# rp3a0-mini-misc.net
KiCad netlist of a schematic drawn in Altium Designer
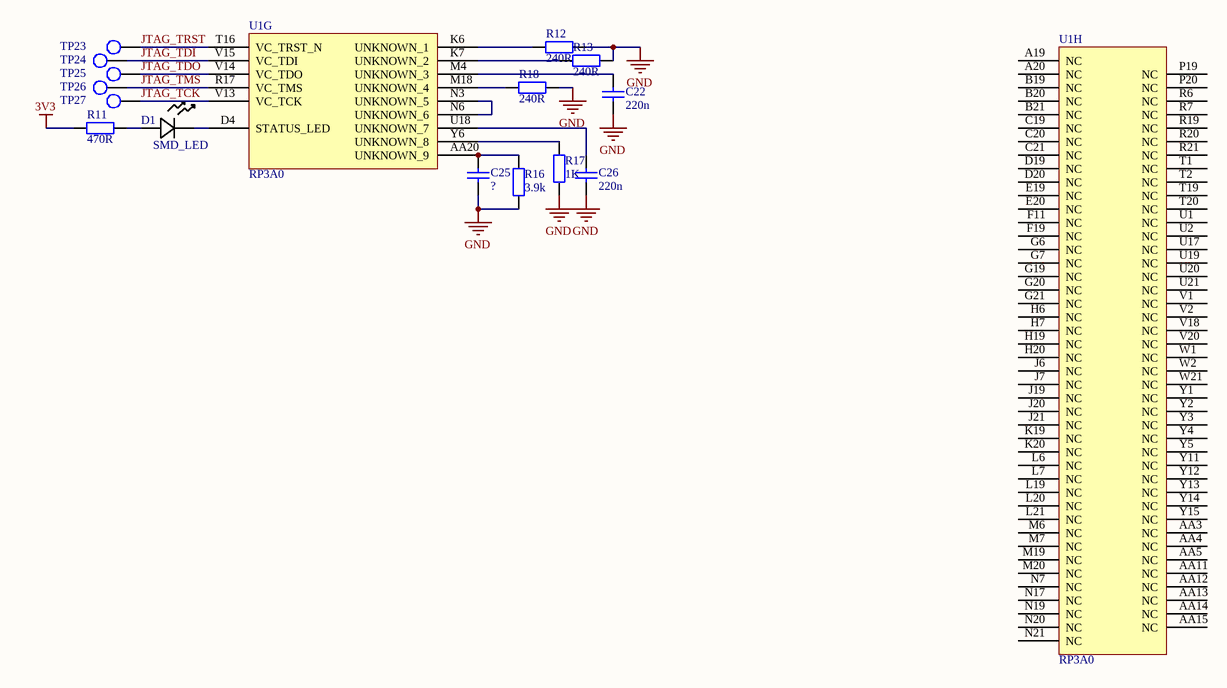
[diagram p0: rp3a0-mini-misc.SchDoc]

(export (version "E")
  (design (tool "Eeschema 10.0.6"))
  (components
    (comp (ref "C22")
      (value "220n")
      (footprint "0402")
      (description "Capacitor")
      (fields (field (name "Comment") "Cap"))
      (libsource (lib "custom-lib") (part "CAP-NONPOL"))
    )
    (comp (ref "C25")
      (value "?")
      (footprint "0402")
      (description "Capacitor")
      (fields (field (name "Comment") "Cap"))
      (libsource (lib "custom-lib") (part "CAP-NONPOL"))
    )
    (comp (ref "C26")
      (value "220n")
      (footprint "0402")
      (description "Capacitor")
      (fields (field (name "Comment") "Cap"))
      (libsource (lib "custom-lib") (part "CAP-NONPOL"))
    )
    (comp (ref "D1") (value "SMD_LED") (footprint "LED_0603") (libsource (lib "custom-lib") (part "SMD_LED")))
    (comp (ref "R11")
      (value "470R")
      (footprint "RES-0402-SML")
      (description "Resistor")
      (fields (field (name "Comment") "Res SMD"))
      (libsource (lib "custom-lib") (part "Res SMD"))
    )
    (comp (ref "R12")
      (value "240R")
      (footprint "RES-0402-SML")
      (description "Resistor")
      (fields (field (name "Comment") "Res SMD"))
      (libsource (lib "custom-lib") (part "Res SMD"))
    )
    (comp (ref "R13")
      (value "240R")
      (footprint "RES-0402-SML")
      (description "Resistor")
      (fields (field (name "Comment") "Res SMD"))
      (libsource (lib "custom-lib") (part "Res SMD"))
    )
    (comp (ref "R16")
      (value "3.9k")
      (footprint "RES-0402-SML")
      (description "Resistor")
      (fields (field (name "Comment") "Res SMD"))
      (libsource (lib "") (part "Res SMD_1"))
    )
    (comp (ref "R17")
      (value "1K")
      (footprint "RES-0402-SML")
      (description "Resistor")
      (fields (field (name "Comment") "Res SMD"))
      (libsource (lib "") (part "Res SMD_1"))
    )
    (comp (ref "R18")
      (value "240R")
      (footprint "RES-0402-SML")
      (description "Resistor")
      (fields (field (name "Comment") "Res SMD"))
      (libsource (lib "custom-lib") (part "Res SMD"))
    )
    (comp (ref "TP23")
      (value "TEST_POINT")
      (footprint "TEST_POINT_1.2MM")
      (description "Test point")
      (libsource (lib "custom-lib") (part "TEST_POINT"))
    )
    (comp (ref "TP24")
      (value "TEST_POINT")
      (footprint "TEST_POINT_1.2MM")
      (description "Test point")
      (libsource (lib "custom-lib") (part "TEST_POINT"))
    )
    (comp (ref "TP25")
      (value "TEST_POINT")
      (footprint "TEST_POINT_1.2MM")
      (description "Test point")
      (libsource (lib "custom-lib") (part "TEST_POINT"))
    )
    (comp (ref "TP26")
      (value "TEST_POINT")
      (footprint "TEST_POINT_1.2MM")
      (description "Test point")
      (libsource (lib "custom-lib") (part "TEST_POINT"))
    )
    (comp (ref "TP27")
      (value "TEST_POINT")
      (footprint "TEST_POINT_1.2MM")
      (description "Test point")
      (libsource (lib "custom-lib") (part "TEST_POINT"))
    )
    (comp (ref "U1") (value "RP3A0") (footprint "RP3A0-BGA") (libsource (lib "rp3a0") (part "RP3A0")))
  )
  (nets
    (net (code "1") (name "/JTAG_TCK") (class "Default")
      (node (ref "TP27") (pin "TP") (pintype "passive"))
      (node (ref "U1") (pin "V13") (pinfunction "VC_TCK_V13") (pintype "passive"))
    )
    (net (code "2") (name "/JTAG_TDI") (class "Default")
      (node (ref "TP24") (pin "TP") (pintype "passive"))
      (node (ref "U1") (pin "V15") (pinfunction "VC_TDI_V15") (pintype "passive"))
    )
    (net (code "3") (name "/JTAG_TDO") (class "Default")
      (node (ref "TP25") (pin "TP") (pintype "passive"))
      (node (ref "U1") (pin "V14") (pinfunction "VC_TDO_V14") (pintype "passive"))
    )
    (net (code "4") (name "/JTAG_TMS") (class "Default")
      (node (ref "TP26") (pin "TP") (pintype "passive"))
      (node (ref "U1") (pin "R17") (pinfunction "VC_TMS_R17") (pintype "passive"))
    )
    (net (code "5") (name "/JTAG_TRST") (class "Default")
      (node (ref "TP23") (pin "TP") (pintype "passive"))
      (node (ref "U1") (pin "T16") (pinfunction "VC_TRST_N_T16") (pintype "passive"))
    )
    (net (code "6") (name "3V3") (class "Default")
      (node (ref "R11") (pin "1") (pinfunction "1_1") (pintype "passive"))
    )
    (net (code "7") (name "GND") (class "Default")
      (node (ref "C22") (pin "1") (pinfunction "1_1") (pintype "passive"))
      (node (ref "C25") (pin "1") (pinfunction "1_1") (pintype "passive"))
      (node (ref "C26") (pin "1") (pinfunction "1_1") (pintype "passive"))
      (node (ref "R12") (pin "2") (pinfunction "2_2") (pintype "passive"))
      (node (ref "R13") (pin "2") (pinfunction "2_2") (pintype "passive"))
      (node (ref "R16") (pin "1") (pinfunction "1_1") (pintype "passive"))
      (node (ref "R17") (pin "1") (pinfunction "1_1") (pintype "passive"))
      (node (ref "R18") (pin "2") (pinfunction "2_2") (pintype "passive"))
    )
    (net (code "8") (name "Net-(D1-Pad1)") (class "Default")
      (node (ref "D1") (pin "1") (pinfunction "1_1") (pintype "passive"))
      (node (ref "R11") (pin "2") (pinfunction "2_2") (pintype "passive"))
    )
    (net (code "9") (name "Net-(U1G-STATUS_LED)") (class "Default")
      (node (ref "D1") (pin "2") (pinfunction "2_2") (pintype "passive"))
      (node (ref "U1") (pin "D4") (pinfunction "STATUS_LED_D4") (pintype "passive"))
    )
    (net (code "10") (name "Net-(U1G-UNKNOWN_1)") (class "Default")
      (node (ref "R12") (pin "1") (pinfunction "1_1") (pintype "passive"))
      (node (ref "U1") (pin "K6") (pinfunction "UNKNOWN_1_K6") (pintype "passive"))
    )
    (net (code "11") (name "Net-(U1G-UNKNOWN_2)") (class "Default")
      (node (ref "R13") (pin "1") (pinfunction "1_1") (pintype "passive"))
      (node (ref "U1") (pin "K7") (pinfunction "UNKNOWN_2_K7") (pintype "passive"))
    )
    (net (code "12") (name "Net-(U1G-UNKNOWN_3)") (class "Default")
      (node (ref "C22") (pin "2") (pinfunction "2_2") (pintype "passive"))
      (node (ref "U1") (pin "M4") (pinfunction "UNKNOWN_3_M4") (pintype "passive"))
    )
    (net (code "13") (name "Net-(U1G-UNKNOWN_4)") (class "Default")
      (node (ref "R18") (pin "1") (pinfunction "1_1") (pintype "passive"))
      (node (ref "U1") (pin "M18") (pinfunction "UNKNOWN_4_M18") (pintype "passive"))
    )
    (net (code "14") (name "Net-(U1G-UNKNOWN_5)") (class "Default")
      (node (ref "U1") (pin "N3") (pinfunction "UNKNOWN_5_N3") (pintype "passive"))
      (node (ref "U1") (pin "N6") (pinfunction "UNKNOWN_6_N6") (pintype "passive"))
    )
    (net (code "15") (name "Net-(U1G-UNKNOWN_7)") (class "Default")
      (node (ref "C26") (pin "2") (pinfunction "2_2") (pintype "passive"))
      (node (ref "U1") (pin "U18") (pinfunction "UNKNOWN_7_U18") (pintype "passive"))
    )
    (net (code "16") (name "Net-(U1G-UNKNOWN_8)") (class "Default")
      (node (ref "R17") (pin "2") (pinfunction "2_2") (pintype "passive"))
      (node (ref "U1") (pin "Y6") (pinfunction "UNKNOWN_8_Y6") (pintype "passive"))
    )
    (net (code "17") (name "Net-(U1G-UNKNOWN_9)") (class "Default")
      (node (ref "C25") (pin "2") (pinfunction "2_2") (pintype "passive"))
      (node (ref "R16") (pin "2") (pinfunction "2_2") (pintype "passive"))
      (node (ref "U1") (pin "AA20") (pinfunction "UNKNOWN_9_AA20") (pintype "passive"))
    )
    (net (code "18") (name "unconnected-(U1H-NC-PadA19)") (class "Default")
      (node (ref "U1") (pin "A19") (pinfunction "NC_A19") (pintype "passive"))
    )
    (net (code "19") (name "unconnected-(U1H-NC-PadA20)") (class "Default")
      (node (ref "U1") (pin "A20") (pinfunction "NC_A20") (pintype "passive"))
    )
    (net (code "20") (name "unconnected-(U1H-NC-PadAA3)") (class "Default")
      (node (ref "U1") (pin "AA3") (pinfunction "NC_AA3") (pintype "passive"))
    )
    (net (code "21") (name "unconnected-(U1H-NC-PadAA4)") (class "Default")
      (node (ref "U1") (pin "AA4") (pinfunction "NC_AA4") (pintype "passive"))
    )
    (net (code "22") (name "unconnected-(U1H-NC-PadAA5)") (class "Default")
      (node (ref "U1") (pin "AA5") (pinfunction "NC_AA5") (pintype "passive"))
    )
    (net (code "23") (name "unconnected-(U1H-NC-PadAA11)") (class "Default")
      (node (ref "U1") (pin "AA11") (pinfunction "NC_AA11") (pintype "passive"))
    )
    (net (code "24") (name "unconnected-(U1H-NC-PadAA12)") (class "Default")
      (node (ref "U1") (pin "AA12") (pinfunction "NC_AA12") (pintype "passive"))
    )
    (net (code "25") (name "unconnected-(U1H-NC-PadAA13)") (class "Default")
      (node (ref "U1") (pin "AA13") (pinfunction "NC_AA13") (pintype "passive"))
    )
    (net (code "26") (name "unconnected-(U1H-NC-PadAA14)") (class "Default")
      (node (ref "U1") (pin "AA14") (pinfunction "NC_AA14") (pintype "passive"))
    )
    (net (code "27") (name "unconnected-(U1H-NC-PadAA15)") (class "Default")
      (node (ref "U1") (pin "AA15") (pinfunction "NC_AA15") (pintype "passive"))
    )
    (net (code "28") (name "unconnected-(U1H-NC-PadB19)") (class "Default")
      (node (ref "U1") (pin "B19") (pinfunction "NC_B19") (pintype "passive"))
    )
    (net (code "29") (name "unconnected-(U1H-NC-PadB20)") (class "Default")
      (node (ref "U1") (pin "B20") (pinfunction "NC_B20") (pintype "passive"))
    )
    (net (code "30") (name "unconnected-(U1H-NC-PadB21)") (class "Default")
      (node (ref "U1") (pin "B21") (pinfunction "NC_B21") (pintype "passive"))
    )
    (net (code "31") (name "unconnected-(U1H-NC-PadC19)") (class "Default")
      (node (ref "U1") (pin "C19") (pinfunction "NC_C19") (pintype "passive"))
    )
    (net (code "32") (name "unconnected-(U1H-NC-PadC20)") (class "Default")
      (node (ref "U1") (pin "C20") (pinfunction "NC_C20") (pintype "passive"))
    )
    (net (code "33") (name "unconnected-(U1H-NC-PadC21)") (class "Default")
      (node (ref "U1") (pin "C21") (pinfunction "NC_C21") (pintype "passive"))
    )
    (net (code "34") (name "unconnected-(U1H-NC-PadD19)") (class "Default")
      (node (ref "U1") (pin "D19") (pinfunction "NC_D19") (pintype "passive"))
    )
    (net (code "35") (name "unconnected-(U1H-NC-PadD20)") (class "Default")
      (node (ref "U1") (pin "D20") (pinfunction "NC_D20") (pintype "passive"))
    )
    (net (code "36") (name "unconnected-(U1H-NC-PadE19)") (class "Default")
      (node (ref "U1") (pin "E19") (pinfunction "NC_E19") (pintype "passive"))
    )
    (net (code "37") (name "unconnected-(U1H-NC-PadE20)") (class "Default")
      (node (ref "U1") (pin "E20") (pinfunction "NC_E20") (pintype "passive"))
    )
    (net (code "38") (name "unconnected-(U1H-NC-PadF11)") (class "Default")
      (node (ref "U1") (pin "F11") (pinfunction "NC_F11") (pintype "passive"))
    )
    (net (code "39") (name "unconnected-(U1H-NC-PadF19)") (class "Default")
      (node (ref "U1") (pin "F19") (pinfunction "NC_F19") (pintype "passive"))
    )
    (net (code "40") (name "unconnected-(U1H-NC-PadG6)") (class "Default")
      (node (ref "U1") (pin "G6") (pinfunction "NC_G6") (pintype "passive"))
    )
    (net (code "41") (name "unconnected-(U1H-NC-PadG7)") (class "Default")
      (node (ref "U1") (pin "G7") (pinfunction "NC_G7") (pintype "passive"))
    )
    (net (code "42") (name "unconnected-(U1H-NC-PadG19)") (class "Default")
      (node (ref "U1") (pin "G19") (pinfunction "NC_G19") (pintype "passive"))
    )
    (net (code "43") (name "unconnected-(U1H-NC-PadG20)") (class "Default")
      (node (ref "U1") (pin "G20") (pinfunction "NC_G20") (pintype "passive"))
    )
    (net (code "44") (name "unconnected-(U1H-NC-PadG21)") (class "Default")
      (node (ref "U1") (pin "G21") (pinfunction "NC_G21") (pintype "passive"))
    )
    (net (code "45") (name "unconnected-(U1H-NC-PadH6)") (class "Default")
      (node (ref "U1") (pin "H6") (pinfunction "NC_H6") (pintype "passive"))
    )
    (net (code "46") (name "unconnected-(U1H-NC-PadH7)") (class "Default")
      (node (ref "U1") (pin "H7") (pinfunction "NC_H7") (pintype "passive"))
    )
    (net (code "47") (name "unconnected-(U1H-NC-PadH19)") (class "Default")
      (node (ref "U1") (pin "H19") (pinfunction "NC_H19") (pintype "passive"))
    )
    (net (code "48") (name "unconnected-(U1H-NC-PadH20)") (class "Default")
      (node (ref "U1") (pin "H20") (pinfunction "NC_H20") (pintype "passive"))
    )
    (net (code "49") (name "unconnected-(U1H-NC-PadJ6)") (class "Default")
      (node (ref "U1") (pin "J6") (pinfunction "NC_J6") (pintype "passive"))
    )
    (net (code "50") (name "unconnected-(U1H-NC-PadJ7)") (class "Default")
      (node (ref "U1") (pin "J7") (pinfunction "NC_J7") (pintype "passive"))
    )
    (net (code "51") (name "unconnected-(U1H-NC-PadJ19)") (class "Default")
      (node (ref "U1") (pin "J19") (pinfunction "NC_J19") (pintype "passive"))
    )
    (net (code "52") (name "unconnected-(U1H-NC-PadJ20)") (class "Default")
      (node (ref "U1") (pin "J20") (pinfunction "NC_J20") (pintype "passive"))
    )
    (net (code "53") (name "unconnected-(U1H-NC-PadJ21)") (class "Default")
      (node (ref "U1") (pin "J21") (pinfunction "NC_J21") (pintype "passive"))
    )
    (net (code "54") (name "unconnected-(U1H-NC-PadK19)") (class "Default")
      (node (ref "U1") (pin "K19") (pinfunction "NC_K19") (pintype "passive"))
    )
    (net (code "55") (name "unconnected-(U1H-NC-PadK20)") (class "Default")
      (node (ref "U1") (pin "K20") (pinfunction "NC_K20") (pintype "passive"))
    )
    (net (code "56") (name "unconnected-(U1H-NC-PadL6)") (class "Default")
      (node (ref "U1") (pin "L6") (pinfunction "NC_L6") (pintype "passive"))
    )
    (net (code "57") (name "unconnected-(U1H-NC-PadL7)") (class "Default")
      (node (ref "U1") (pin "L7") (pinfunction "NC_L7") (pintype "passive"))
    )
    (net (code "58") (name "unconnected-(U1H-NC-PadL19)") (class "Default")
      (node (ref "U1") (pin "L19") (pinfunction "NC_L19") (pintype "passive"))
    )
    (net (code "59") (name "unconnected-(U1H-NC-PadL20)") (class "Default")
      (node (ref "U1") (pin "L20") (pinfunction "NC_L20") (pintype "passive"))
    )
    (net (code "60") (name "unconnected-(U1H-NC-PadL21)") (class "Default")
      (node (ref "U1") (pin "L21") (pinfunction "NC_L21") (pintype "passive"))
    )
    (net (code "61") (name "unconnected-(U1H-NC-PadM6)") (class "Default")
      (node (ref "U1") (pin "M6") (pinfunction "NC_M6") (pintype "passive"))
    )
    (net (code "62") (name "unconnected-(U1H-NC-PadM7)") (class "Default")
      (node (ref "U1") (pin "M7") (pinfunction "NC_M7") (pintype "passive"))
    )
    (net (code "63") (name "unconnected-(U1H-NC-PadM19)") (class "Default")
      (node (ref "U1") (pin "M19") (pinfunction "NC_M19") (pintype "passive"))
    )
    (net (code "64") (name "unconnected-(U1H-NC-PadM20)") (class "Default")
      (node (ref "U1") (pin "M20") (pinfunction "NC_M20") (pintype "passive"))
    )
    (net (code "65") (name "unconnected-(U1H-NC-PadN7)") (class "Default")
      (node (ref "U1") (pin "N7") (pinfunction "NC_N7") (pintype "passive"))
    )
    (net (code "66") (name "unconnected-(U1H-NC-PadN17)") (class "Default")
      (node (ref "U1") (pin "N17") (pinfunction "NC_N17") (pintype "passive"))
    )
    (net (code "67") (name "unconnected-(U1H-NC-PadN19)") (class "Default")
      (node (ref "U1") (pin "N19") (pinfunction "NC_N19") (pintype "passive"))
    )
    (net (code "68") (name "unconnected-(U1H-NC-PadN20)") (class "Default")
      (node (ref "U1") (pin "N20") (pinfunction "NC_N20") (pintype "passive"))
    )
    (net (code "69") (name "unconnected-(U1H-NC-PadN21)") (class "Default")
      (node (ref "U1") (pin "N21") (pinfunction "NC_N21") (pintype "passive"))
    )
    (net (code "70") (name "unconnected-(U1H-NC-PadP19)") (class "Default")
      (node (ref "U1") (pin "P19") (pinfunction "NC_P19") (pintype "passive"))
    )
    (net (code "71") (name "unconnected-(U1H-NC-PadP20)") (class "Default")
      (node (ref "U1") (pin "P20") (pinfunction "NC_P20") (pintype "passive"))
    )
    (net (code "72") (name "unconnected-(U1H-NC-PadR6)") (class "Default")
      (node (ref "U1") (pin "R6") (pinfunction "NC_R6") (pintype "passive"))
    )
    (net (code "73") (name "unconnected-(U1H-NC-PadR7)") (class "Default")
      (node (ref "U1") (pin "R7") (pinfunction "NC_R7") (pintype "passive"))
    )
    (net (code "74") (name "unconnected-(U1H-NC-PadR19)") (class "Default")
      (node (ref "U1") (pin "R19") (pinfunction "NC_R19") (pintype "passive"))
    )
    (net (code "75") (name "unconnected-(U1H-NC-PadR20)") (class "Default")
      (node (ref "U1") (pin "R20") (pinfunction "NC_R20") (pintype "passive"))
    )
    (net (code "76") (name "unconnected-(U1H-NC-PadR21)") (class "Default")
      (node (ref "U1") (pin "R21") (pinfunction "NC_R21") (pintype "passive"))
    )
    (net (code "77") (name "unconnected-(U1H-NC-PadT1)") (class "Default")
      (node (ref "U1") (pin "T1") (pinfunction "NC_T1") (pintype "passive"))
    )
    (net (code "78") (name "unconnected-(U1H-NC-PadT2)") (class "Default")
      (node (ref "U1") (pin "T2") (pinfunction "NC_T2") (pintype "passive"))
    )
    (net (code "79") (name "unconnected-(U1H-NC-PadT19)") (class "Default")
      (node (ref "U1") (pin "T19") (pinfunction "NC_T19") (pintype "passive"))
    )
    (net (code "80") (name "unconnected-(U1H-NC-PadT20)") (class "Default")
      (node (ref "U1") (pin "T20") (pinfunction "NC_T20") (pintype "passive"))
    )
    (net (code "81") (name "unconnected-(U1H-NC-PadU1)") (class "Default")
      (node (ref "U1") (pin "U1") (pinfunction "NC_U1") (pintype "passive"))
    )
    (net (code "82") (name "unconnected-(U1H-NC-PadU2)") (class "Default")
      (node (ref "U1") (pin "U2") (pinfunction "NC_U2") (pintype "passive"))
    )
    (net (code "83") (name "unconnected-(U1H-NC-PadU17)") (class "Default")
      (node (ref "U1") (pin "U17") (pinfunction "NC_U17") (pintype "passive"))
    )
    (net (code "84") (name "unconnected-(U1H-NC-PadU19)") (class "Default")
      (node (ref "U1") (pin "U19") (pinfunction "NC_U19") (pintype "passive"))
    )
    (net (code "85") (name "unconnected-(U1H-NC-PadU20)") (class "Default")
      (node (ref "U1") (pin "U20") (pinfunction "NC_U20") (pintype "passive"))
    )
    (net (code "86") (name "unconnected-(U1H-NC-PadU21)") (class "Default")
      (node (ref "U1") (pin "U21") (pinfunction "NC_U21") (pintype "passive"))
    )
    (net (code "87") (name "unconnected-(U1H-NC-PadV1)") (class "Default")
      (node (ref "U1") (pin "V1") (pinfunction "NC_V1") (pintype "passive"))
    )
    (net (code "88") (name "unconnected-(U1H-NC-PadV2)") (class "Default")
      (node (ref "U1") (pin "V2") (pinfunction "NC_V2") (pintype "passive"))
    )
    (net (code "89") (name "unconnected-(U1H-NC-PadV18)") (class "Default")
      (node (ref "U1") (pin "V18") (pinfunction "NC_V18") (pintype "passive"))
    )
    (net (code "90") (name "unconnected-(U1H-NC-PadV20)") (class "Default")
      (node (ref "U1") (pin "V20") (pinfunction "NC_V20") (pintype "passive"))
    )
    (net (code "91") (name "unconnected-(U1H-NC-PadW1)") (class "Default")
      (node (ref "U1") (pin "W1") (pinfunction "NC_W1") (pintype "passive"))
    )
    (net (code "92") (name "unconnected-(U1H-NC-PadW2)") (class "Default")
      (node (ref "U1") (pin "W2") (pinfunction "NC_W2") (pintype "passive"))
    )
    (net (code "93") (name "unconnected-(U1H-NC-PadW21)") (class "Default")
      (node (ref "U1") (pin "W21") (pinfunction "NC_W21") (pintype "passive"))
    )
    (net (code "94") (name "unconnected-(U1H-NC-PadY1)") (class "Default")
      (node (ref "U1") (pin "Y1") (pinfunction "NC_Y1") (pintype "passive"))
    )
    (net (code "95") (name "unconnected-(U1H-NC-PadY2)") (class "Default")
      (node (ref "U1") (pin "Y2") (pinfunction "NC_Y2") (pintype "passive"))
    )
    (net (code "96") (name "unconnected-(U1H-NC-PadY3)") (class "Default")
      (node (ref "U1") (pin "Y3") (pinfunction "NC_Y3") (pintype "passive"))
    )
    (net (code "97") (name "unconnected-(U1H-NC-PadY4)") (class "Default")
      (node (ref "U1") (pin "Y4") (pinfunction "NC_Y4") (pintype "passive"))
    )
    (net (code "98") (name "unconnected-(U1H-NC-PadY5)") (class "Default")
      (node (ref "U1") (pin "Y5") (pinfunction "NC_Y5") (pintype "passive"))
    )
    (net (code "99") (name "unconnected-(U1H-NC-PadY11)") (class "Default")
      (node (ref "U1") (pin "Y11") (pinfunction "NC_Y11") (pintype "passive"))
    )
    (net (code "100") (name "unconnected-(U1H-NC-PadY12)") (class "Default")
      (node (ref "U1") (pin "Y12") (pinfunction "NC_Y12") (pintype "passive"))
    )
    (net (code "101") (name "unconnected-(U1H-NC-PadY13)") (class "Default")
      (node (ref "U1") (pin "Y13") (pinfunction "NC_Y13") (pintype "passive"))
    )
    (net (code "102") (name "unconnected-(U1H-NC-PadY14)") (class "Default")
      (node (ref "U1") (pin "Y14") (pinfunction "NC_Y14") (pintype "passive"))
    )
    (net (code "103") (name "unconnected-(U1H-NC-PadY15)") (class "Default")
      (node (ref "U1") (pin "Y15") (pinfunction "NC_Y15") (pintype "passive"))
    )
  )
)
